# Main.net
KiCad netlist of a schematic drawn in Altium Designer
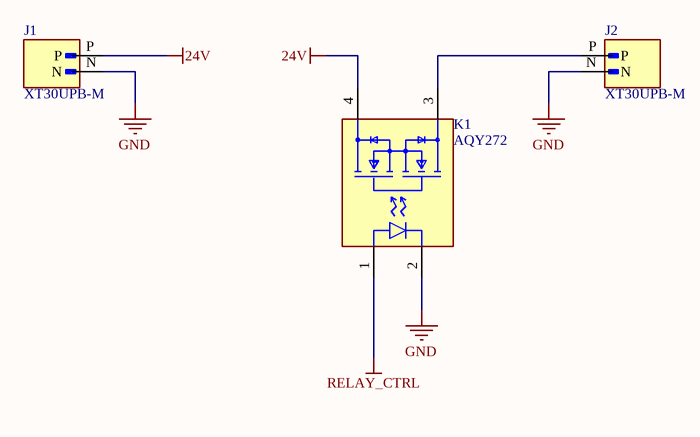
[diagram p0: Main.SchDoc]

(export (version "E")
  (design (tool "Eeschema 10.0.6"))
  (components
    (comp (ref "J1")
      (value "XT30UPB-M")
      (footprint "AMASS_XT30UPB-M")
      (description "Socket; DC supply; XT30; male; PIN: 2; on PCBs; THT; yellow; 15A; 500V")
      (fields (field (name "MF") "amass"))
      (libsource (lib "XT30UPB-M") (part "XT30UPB-M"))
    )
    (comp (ref "J2")
      (value "XT30UPB-M")
      (footprint "AMASS_XT30UPB-M")
      (description "Socket; DC supply; XT30; male; PIN: 2; on PCBs; THT; yellow; 15A; 500V")
      (fields (field (name "MF") "amass"))
      (libsource (lib "") (part "XT30UPB-M_1"))
    )
    (comp (ref "K1")
      (value "AQY272")
      (footprint "FP-AQY272-MFG")
      (description "SSR RELAY SPST-NO 2A 0-60V")
      (libsource (lib "Altium Content Vault") (part "b48b7fcafc852751f620c383186d6b0"))
    )
  )
  (nets
    (net (code "1") (name "24V") (class "Default")
      (node (ref "J1") (pin "P") (pinfunction "P_P") (pintype "passive"))
      (node (ref "K1") (pin "4") (pinfunction "2_DRAIN_4") (pintype "passive"))
    )
    (net (code "2") (name "GND") (class "Default")
      (node (ref "J1") (pin "N") (pinfunction "N_N") (pintype "passive"))
      (node (ref "J2") (pin "N") (pinfunction "N_N") (pintype "passive"))
      (node (ref "K1") (pin "2") (pinfunction "C_2") (pintype "passive"))
    )
    (net (code "3") (name "Net-(K1-1_DRAIN)") (class "Default")
      (node (ref "J2") (pin "P") (pinfunction "P_P") (pintype "passive"))
      (node (ref "K1") (pin "3") (pinfunction "1_DRAIN_3") (pintype "passive"))
    )
    (net (code "4") (name "RELAY_CTRL") (class "Default")
      (node (ref "K1") (pin "1") (pinfunction "A_1") (pintype "passive"))
    )
  )
)
